# power.net
KiCad netlist of a schematic drawn in EAGLE
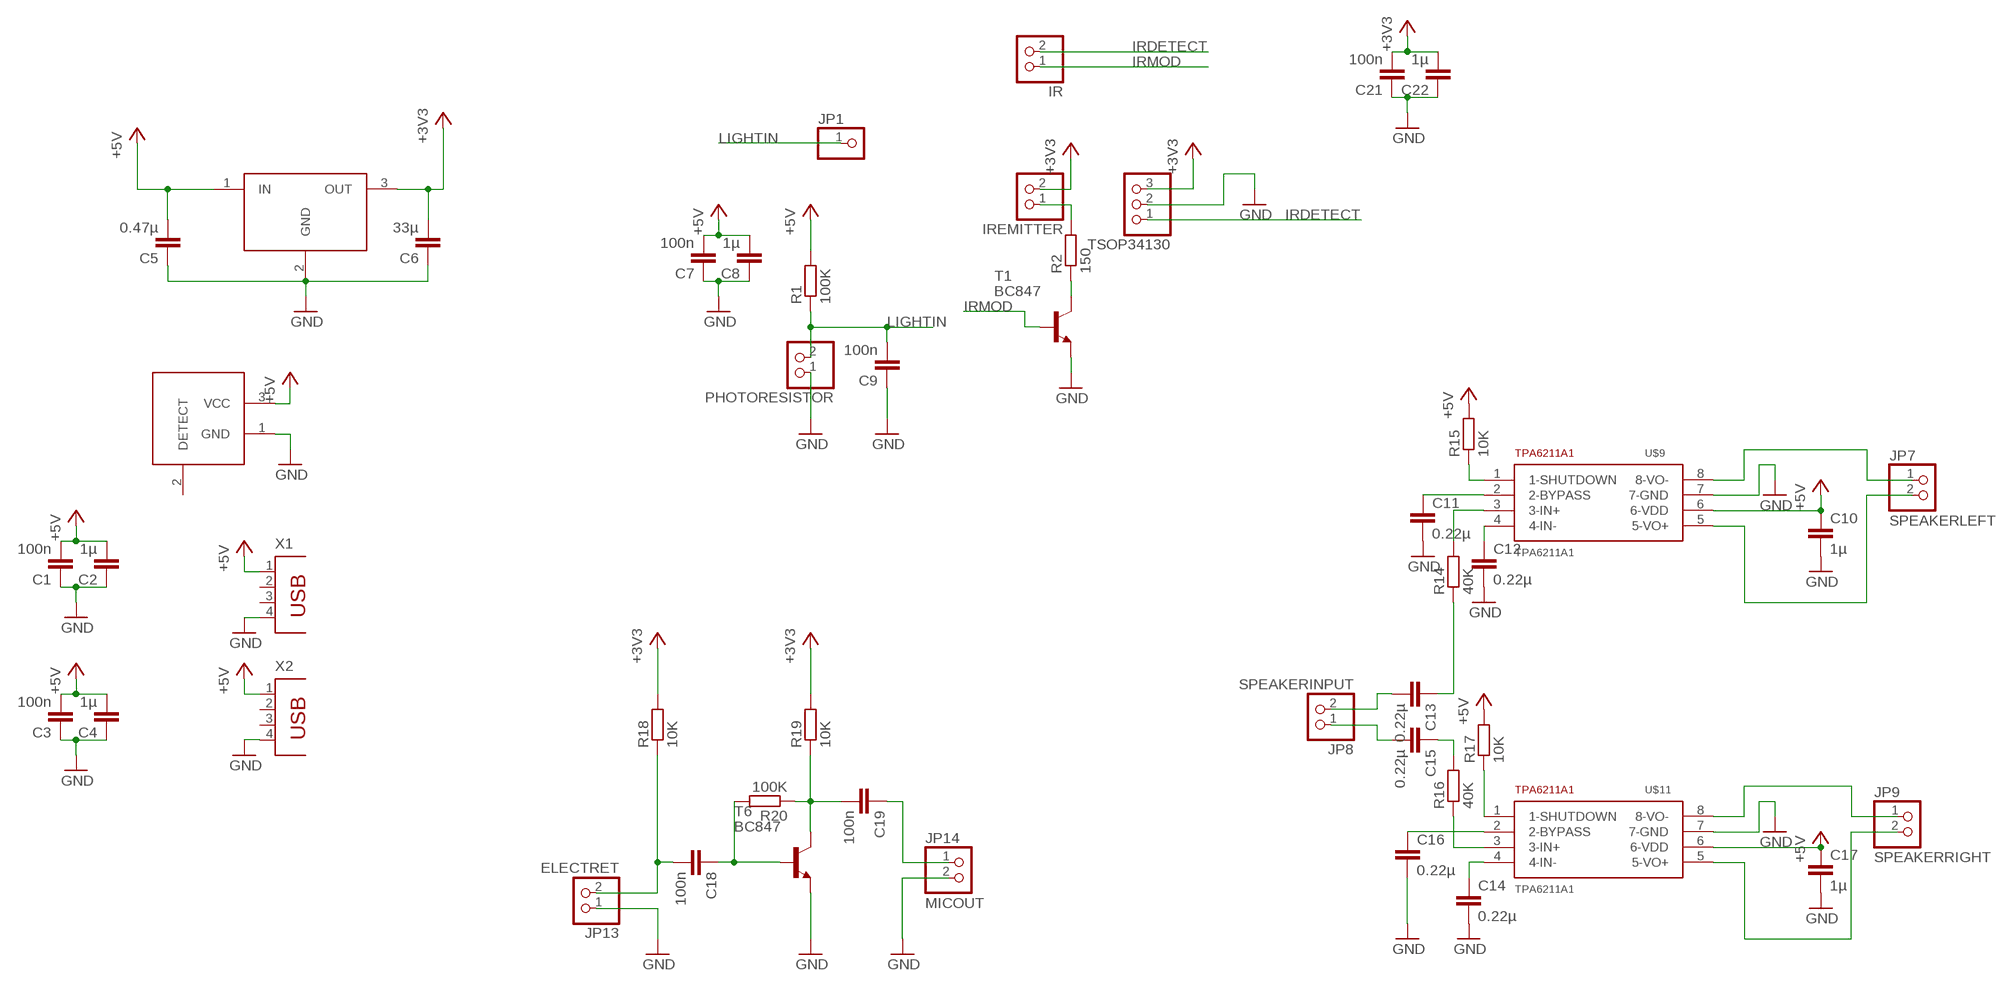
[diagram p0: schematic, sheet 1]

(export (version "E")
  (design (tool "Eeschema 10.0.6"))
  (components
    (comp (ref "C1")
      (value "100n")
      (footprint "eagle-import:C0805")
      (libsource (lib "eagle-import") (part "C-EUC0805"))
    )
    (comp (ref "C2")
      (value "1µ")
      (footprint "eagle-import:C0805")
      (libsource (lib "eagle-import") (part "C-EUC0805"))
    )
    (comp (ref "C3")
      (value "100n")
      (footprint "eagle-import:C0805")
      (libsource (lib "eagle-import") (part "C-EUC0805"))
    )
    (comp (ref "C4")
      (value "1µ")
      (footprint "eagle-import:C0805")
      (libsource (lib "eagle-import") (part "C-EUC0805"))
    )
    (comp (ref "C5")
      (value "0.47µ")
      (footprint "eagle-import:C0805")
      (libsource (lib "eagle-import") (part "C-EUC0805"))
    )
    (comp (ref "C6")
      (value "33µ")
      (footprint "eagle-import:C0805")
      (libsource (lib "eagle-import") (part "C-EUC0805"))
    )
    (comp (ref "C7")
      (value "100n")
      (footprint "eagle-import:C0805")
      (libsource (lib "eagle-import") (part "C-EUC0805"))
    )
    (comp (ref "C8")
      (value "1µ")
      (footprint "eagle-import:C0805")
      (libsource (lib "eagle-import") (part "C-EUC0805"))
    )
    (comp (ref "C9")
      (value "100n")
      (footprint "eagle-import:C0805")
      (libsource (lib "eagle-import") (part "C-EUC0805"))
    )
    (comp (ref "C10")
      (value "1µ")
      (footprint "eagle-import:C0805")
      (libsource (lib "eagle-import") (part "C-EUC0805"))
    )
    (comp (ref "C11")
      (value "0.22µ")
      (footprint "eagle-import:C0805")
      (libsource (lib "eagle-import") (part "C-EUC0805"))
    )
    (comp (ref "C12")
      (value "0.22µ")
      (footprint "eagle-import:C0805")
      (libsource (lib "eagle-import") (part "C-EUC0805"))
    )
    (comp (ref "C13")
      (value "0.22µ")
      (footprint "eagle-import:C0805")
      (libsource (lib "eagle-import") (part "C-EUC0805"))
    )
    (comp (ref "C14")
      (value "0.22µ")
      (footprint "eagle-import:C0805")
      (libsource (lib "eagle-import") (part "C-EUC0805"))
    )
    (comp (ref "C15")
      (value "0.22µ")
      (footprint "eagle-import:C0805")
      (libsource (lib "eagle-import") (part "C-EUC0805"))
    )
    (comp (ref "C16")
      (value "0.22µ")
      (footprint "eagle-import:C0805")
      (libsource (lib "eagle-import") (part "C-EUC0805"))
    )
    (comp (ref "C17")
      (value "1µ")
      (footprint "eagle-import:C0805")
      (libsource (lib "eagle-import") (part "C-EUC0805"))
    )
    (comp (ref "C18")
      (value "100n")
      (footprint "eagle-import:C0805")
      (libsource (lib "eagle-import") (part "C-EUC0805"))
    )
    (comp (ref "C19")
      (value "100n")
      (footprint "eagle-import:C0805")
      (libsource (lib "eagle-import") (part "C-EUC0805"))
    )
    (comp (ref "C21")
      (value "100n")
      (footprint "eagle-import:C0805")
      (libsource (lib "eagle-import") (part "C-EUC0805"))
    )
    (comp (ref "C22")
      (value "1µ")
      (footprint "eagle-import:C0805")
      (libsource (lib "eagle-import") (part "C-EUC0805"))
    )
    (comp (ref "IR")
      (value "PINHD-1X2")
      (footprint "eagle-import:1X02")
      (libsource (lib "eagle-import") (part "PINHD-1X2"))
    )
    (comp (ref "IREMITTER")
      (value "PINHD-1X2")
      (footprint "eagle-import:1X02")
      (libsource (lib "eagle-import") (part "PINHD-1X2"))
    )
    (comp (ref "JP1")
      (value "PINHD-1X1")
      (footprint "eagle-import:1X01")
      (libsource (lib "eagle-import") (part "PINHD-1X1"))
    )
    (comp (ref "JP7")
      (value "SPEAKERLEFT")
      (footprint "eagle-import:1X02")
      (libsource (lib "eagle-import") (part "PINHD-1X2"))
    )
    (comp (ref "JP8")
      (value "SPEAKERINPUT")
      (footprint "eagle-import:1X02")
      (libsource (lib "eagle-import") (part "PINHD-1X2"))
    )
    (comp (ref "JP9")
      (value "SPEAKERRIGHT")
      (footprint "eagle-import:1X02")
      (libsource (lib "eagle-import") (part "PINHD-1X2"))
    )
    (comp (ref "JP13")
      (value "ELECTRET")
      (footprint "eagle-import:1X02")
      (libsource (lib "eagle-import") (part "PINHD-1X2"))
    )
    (comp (ref "JP14")
      (value "MICOUT")
      (footprint "eagle-import:1X02")
      (libsource (lib "eagle-import") (part "PINHD-1X2"))
    )
    (comp (ref "PHOTORESISTOR")
      (value "PINHD-1X2")
      (footprint "eagle-import:1X02")
      (libsource (lib "eagle-import") (part "PINHD-1X2"))
    )
    (comp (ref "R1")
      (value "100K")
      (footprint "eagle-import:R0805")
      (libsource (lib "eagle-import") (part "R-EU_R0805"))
    )
    (comp (ref "R2")
      (value "150")
      (footprint "eagle-import:R0805")
      (libsource (lib "eagle-import") (part "R-EU_R0805"))
    )
    (comp (ref "R14")
      (value "40K")
      (footprint "eagle-import:R0805")
      (libsource (lib "eagle-import") (part "R-EU_R0805"))
    )
    (comp (ref "R15")
      (value "10K")
      (footprint "eagle-import:R0805")
      (libsource (lib "eagle-import") (part "R-EU_R0805"))
    )
    (comp (ref "R16")
      (value "40K")
      (footprint "eagle-import:R0805")
      (libsource (lib "eagle-import") (part "R-EU_R0805"))
    )
    (comp (ref "R17")
      (value "10K")
      (footprint "eagle-import:R0805")
      (libsource (lib "eagle-import") (part "R-EU_R0805"))
    )
    (comp (ref "R18")
      (value "10K")
      (footprint "eagle-import:R0805")
      (libsource (lib "eagle-import") (part "R-EU_R0805"))
    )
    (comp (ref "R19")
      (value "10K")
      (footprint "eagle-import:R0805")
      (libsource (lib "eagle-import") (part "R-EU_R0805"))
    )
    (comp (ref "R20")
      (value "100K")
      (footprint "eagle-import:R0805")
      (libsource (lib "eagle-import") (part "R-EU_R0805"))
    )
    (comp (ref "T1")
      (value "BC847")
      (footprint "eagle-import:SOT23")
      (libsource (lib "eagle-import") (part "BC847"))
    )
    (comp (ref "T6")
      (value "BC847")
      (footprint "eagle-import:SOT23")
      (libsource (lib "eagle-import") (part "BC847"))
    )
    (comp (ref "TSOP34130")
      (value "PINHD-1X3")
      (footprint "eagle-import:1X03")
      (libsource (lib "eagle-import") (part "PINHD-1X3"))
    )
    (comp (ref "U$1")
      (value "LM3940IMP-3.3")
      (footprint "eagle-import:SOT223")
      (libsource (lib "eagle-import") (part "LM3940IMP-3.3"))
    )
    (comp (ref "U$2")
      (value "POWERPLUG")
      (footprint "eagle-import:DC10LPSOCKET")
      (libsource (lib "eagle-import") (part "POWERPLUG"))
    )
    (comp (ref "U$9")
      (value "TPA6211A1")
      (footprint "eagle-import:MSOP8")
      (libsource (lib "eagle-import") (part "TPA6211A1"))
    )
    (comp (ref "U$11")
      (value "TPA6211A1")
      (footprint "eagle-import:MSOP8")
      (libsource (lib "eagle-import") (part "TPA6211A1"))
    )
    (comp (ref "X1")
      (value "PN87520")
      (footprint "eagle-import:PN87520")
      (libsource (lib "eagle-import") (part "PN87520"))
    )
    (comp (ref "X2")
      (value "PN87520")
      (footprint "eagle-import:PN87520")
      (libsource (lib "eagle-import") (part "PN87520"))
    )
  )
  (nets
    (net (code "1") (name "+3V3") (class "Default")
      (node (ref "C21") (pin "2") (pinfunction "2_2") (pintype "passive"))
      (node (ref "C22") (pin "2") (pinfunction "2_2") (pintype "passive"))
      (node (ref "C6") (pin "2") (pinfunction "2_2") (pintype "passive"))
      (node (ref "IREMITTER") (pin "2") (pinfunction "2_2") (pintype "passive"))
      (node (ref "R18") (pin "2") (pinfunction "2_2") (pintype "passive"))
      (node (ref "R19") (pin "2") (pinfunction "2_2") (pintype "passive"))
      (node (ref "TSOP34130") (pin "3") (pinfunction "3_3") (pintype "passive"))
      (node (ref "U$1") (pin "3") (pinfunction "OUT_3") (pintype "power_in"))
    )
    (net (code "2") (name "+5V") (class "Default")
      (node (ref "C1") (pin "2") (pinfunction "2_2") (pintype "passive"))
      (node (ref "C10") (pin "1") (pinfunction "1_1") (pintype "passive"))
      (node (ref "C17") (pin "1") (pinfunction "1_1") (pintype "passive"))
      (node (ref "C2") (pin "2") (pinfunction "2_2") (pintype "passive"))
      (node (ref "C3") (pin "2") (pinfunction "2_2") (pintype "passive"))
      (node (ref "C4") (pin "2") (pinfunction "2_2") (pintype "passive"))
      (node (ref "C5") (pin "2") (pinfunction "2_2") (pintype "passive"))
      (node (ref "C7") (pin "2") (pinfunction "2_2") (pintype "passive"))
      (node (ref "C8") (pin "2") (pinfunction "2_2") (pintype "passive"))
      (node (ref "R1") (pin "2") (pinfunction "2_2") (pintype "passive"))
      (node (ref "R15") (pin "2") (pinfunction "2_2") (pintype "passive"))
      (node (ref "R17") (pin "2") (pinfunction "2_2") (pintype "passive"))
      (node (ref "U$1") (pin "1") (pinfunction "IN_1") (pintype "power_in"))
      (node (ref "U$11") (pin "6") (pinfunction "6-VDD_6") (pintype "bidirectional"))
      (node (ref "U$2") (pin "3") (pinfunction "VCC_3") (pintype "bidirectional"))
      (node (ref "U$9") (pin "6") (pinfunction "6-VDD_6") (pintype "bidirectional"))
      (node (ref "X1") (pin "1") (pinfunction "1_1") (pintype "passive"))
      (node (ref "X2") (pin "1") (pinfunction "1_1") (pintype "passive"))
    )
    (net (code "3") (name "/IRDETECT") (class "Default")
      (node (ref "IR") (pin "2") (pinfunction "2_2") (pintype "passive"))
      (node (ref "TSOP34130") (pin "1") (pinfunction "1_1") (pintype "passive"))
    )
    (net (code "4") (name "/IRMOD") (class "Default")
      (node (ref "IR") (pin "1") (pinfunction "1_1") (pintype "passive"))
      (node (ref "T1") (pin "1") (pinfunction "B_1") (pintype "passive"))
    )
    (net (code "5") (name "/LIGHTIN") (class "Default")
      (node (ref "C9") (pin "2") (pinfunction "2_2") (pintype "passive"))
      (node (ref "JP1") (pin "1") (pinfunction "1_1") (pintype "passive"))
      (node (ref "PHOTORESISTOR") (pin "2") (pinfunction "2_2") (pintype "passive"))
      (node (ref "R1") (pin "1") (pinfunction "1_1") (pintype "passive"))
    )
    (net (code "6") (name "GND") (class "Default")
      (node (ref "C1") (pin "1") (pinfunction "1_1") (pintype "passive"))
      (node (ref "C10") (pin "2") (pinfunction "2_2") (pintype "passive"))
      (node (ref "C11") (pin "2") (pinfunction "2_2") (pintype "passive"))
      (node (ref "C12") (pin "2") (pinfunction "2_2") (pintype "passive"))
      (node (ref "C14") (pin "2") (pinfunction "2_2") (pintype "passive"))
      (node (ref "C16") (pin "2") (pinfunction "2_2") (pintype "passive"))
      (node (ref "C17") (pin "2") (pinfunction "2_2") (pintype "passive"))
      (node (ref "C2") (pin "1") (pinfunction "1_1") (pintype "passive"))
      (node (ref "C21") (pin "1") (pinfunction "1_1") (pintype "passive"))
      (node (ref "C22") (pin "1") (pinfunction "1_1") (pintype "passive"))
      (node (ref "C3") (pin "1") (pinfunction "1_1") (pintype "passive"))
      (node (ref "C4") (pin "1") (pinfunction "1_1") (pintype "passive"))
      (node (ref "C5") (pin "1") (pinfunction "1_1") (pintype "passive"))
      (node (ref "C6") (pin "1") (pinfunction "1_1") (pintype "passive"))
      (node (ref "C7") (pin "1") (pinfunction "1_1") (pintype "passive"))
      (node (ref "C8") (pin "1") (pinfunction "1_1") (pintype "passive"))
      (node (ref "C9") (pin "1") (pinfunction "1_1") (pintype "passive"))
      (node (ref "JP13") (pin "1") (pinfunction "1_1") (pintype "passive"))
      (node (ref "JP14") (pin "2") (pinfunction "2_2") (pintype "passive"))
      (node (ref "PHOTORESISTOR") (pin "1") (pinfunction "1_1") (pintype "passive"))
      (node (ref "T1") (pin "2") (pinfunction "E_2") (pintype "passive"))
      (node (ref "T6") (pin "2") (pinfunction "E_2") (pintype "passive"))
      (node (ref "TSOP34130") (pin "2") (pinfunction "2_2") (pintype "passive"))
      (node (ref "U$1") (pin "2") (pinfunction "GND_2") (pintype "power_in"))
      (node (ref "U$11") (pin "7") (pinfunction "7-GND_7") (pintype "bidirectional"))
      (node (ref "U$2") (pin "1") (pinfunction "GND_1") (pintype "bidirectional"))
      (node (ref "U$9") (pin "7") (pinfunction "7-GND_7") (pintype "bidirectional"))
      (node (ref "X1") (pin "4") (pinfunction "4_4") (pintype "passive"))
      (node (ref "X2") (pin "4") (pinfunction "4_4") (pintype "passive"))
    )
    (net (code "7") (name "Net-(C13-Pad1)") (class "Default")
      (node (ref "C13") (pin "1") (pinfunction "1_1") (pintype "passive"))
      (node (ref "R14") (pin "1") (pinfunction "1_1") (pintype "passive"))
    )
    (net (code "8") (name "Net-(C13-Pad2)") (class "Default")
      (node (ref "C13") (pin "2") (pinfunction "2_2") (pintype "passive"))
      (node (ref "JP8") (pin "2") (pinfunction "2_2") (pintype "passive"))
    )
    (net (code "9") (name "Net-(C15-Pad1)") (class "Default")
      (node (ref "C15") (pin "1") (pinfunction "1_1") (pintype "passive"))
      (node (ref "R16") (pin "2") (pinfunction "2_2") (pintype "passive"))
    )
    (net (code "10") (name "Net-(C15-Pad2)") (class "Default")
      (node (ref "C15") (pin "2") (pinfunction "2_2") (pintype "passive"))
      (node (ref "JP8") (pin "1") (pinfunction "1_1") (pintype "passive"))
    )
    (net (code "11") (name "Net-(C18-Pad2)") (class "Default")
      (node (ref "C18") (pin "2") (pinfunction "2_2") (pintype "passive"))
      (node (ref "JP13") (pin "2") (pinfunction "2_2") (pintype "passive"))
      (node (ref "R18") (pin "1") (pinfunction "1_1") (pintype "passive"))
    )
    (net (code "12") (name "Net-(C19-Pad1)") (class "Default")
      (node (ref "C19") (pin "1") (pinfunction "1_1") (pintype "passive"))
      (node (ref "JP14") (pin "1") (pinfunction "1_1") (pintype "passive"))
    )
    (net (code "13") (name "Net-(IREMITTER-Pad1)") (class "Default")
      (node (ref "IREMITTER") (pin "1") (pinfunction "1_1") (pintype "passive"))
      (node (ref "R2") (pin "2") (pinfunction "2_2") (pintype "passive"))
    )
    (net (code "14") (name "Net-(T1-C)") (class "Default")
      (node (ref "R2") (pin "1") (pinfunction "1_1") (pintype "passive"))
      (node (ref "T1") (pin "3") (pinfunction "C_3") (pintype "passive"))
    )
    (net (code "15") (name "Net-(T6-B)") (class "Default")
      (node (ref "C18") (pin "1") (pinfunction "1_1") (pintype "passive"))
      (node (ref "R20") (pin "2") (pinfunction "2_2") (pintype "passive"))
      (node (ref "T6") (pin "1") (pinfunction "B_1") (pintype "passive"))
    )
    (net (code "16") (name "Net-(T6-C)") (class "Default")
      (node (ref "C19") (pin "2") (pinfunction "2_2") (pintype "passive"))
      (node (ref "R19") (pin "1") (pinfunction "1_1") (pintype "passive"))
      (node (ref "R20") (pin "1") (pinfunction "1_1") (pintype "passive"))
      (node (ref "T6") (pin "3") (pinfunction "C_3") (pintype "passive"))
    )
    (net (code "17") (name "Net-(U$9-1-SHUTDOWN)") (class "Default")
      (node (ref "R15") (pin "1") (pinfunction "1_1") (pintype "passive"))
      (node (ref "U$9") (pin "1") (pinfunction "1-SHUTDOWN_1") (pintype "bidirectional"))
    )
    (net (code "18") (name "Net-(U$9-2-BYPASS)") (class "Default")
      (node (ref "C11") (pin "1") (pinfunction "1_1") (pintype "passive"))
      (node (ref "U$9") (pin "2") (pinfunction "2-BYPASS_2") (pintype "bidirectional"))
    )
    (net (code "19") (name "Net-(U$9-3-IN+)") (class "Default")
      (node (ref "R14") (pin "2") (pinfunction "2_2") (pintype "passive"))
      (node (ref "U$9") (pin "3") (pinfunction "3-IN+_3") (pintype "bidirectional"))
    )
    (net (code "20") (name "Net-(U$9-4-IN-)") (class "Default")
      (node (ref "C12") (pin "1") (pinfunction "1_1") (pintype "passive"))
      (node (ref "U$9") (pin "4") (pinfunction "4-IN-_4") (pintype "bidirectional"))
    )
    (net (code "21") (name "Net-(U$9-5-VO+)") (class "Default")
      (node (ref "JP7") (pin "2") (pinfunction "2_2") (pintype "passive"))
      (node (ref "U$9") (pin "5") (pinfunction "5-VO+_5") (pintype "bidirectional"))
    )
    (net (code "22") (name "Net-(U$9-8-VO-)") (class "Default")
      (node (ref "JP7") (pin "1") (pinfunction "1_1") (pintype "passive"))
      (node (ref "U$9") (pin "8") (pinfunction "8-VO-_8") (pintype "bidirectional"))
    )
    (net (code "23") (name "Net-(U$11-1-SHUTDOWN)") (class "Default")
      (node (ref "R17") (pin "1") (pinfunction "1_1") (pintype "passive"))
      (node (ref "U$11") (pin "1") (pinfunction "1-SHUTDOWN_1") (pintype "bidirectional"))
    )
    (net (code "24") (name "Net-(U$11-2-BYPASS)") (class "Default")
      (node (ref "C16") (pin "1") (pinfunction "1_1") (pintype "passive"))
      (node (ref "U$11") (pin "2") (pinfunction "2-BYPASS_2") (pintype "bidirectional"))
    )
    (net (code "25") (name "Net-(U$11-3-IN+)") (class "Default")
      (node (ref "R16") (pin "1") (pinfunction "1_1") (pintype "passive"))
      (node (ref "U$11") (pin "3") (pinfunction "3-IN+_3") (pintype "bidirectional"))
    )
    (net (code "26") (name "Net-(U$11-4-IN-)") (class "Default")
      (node (ref "C14") (pin "1") (pinfunction "1_1") (pintype "passive"))
      (node (ref "U$11") (pin "4") (pinfunction "4-IN-_4") (pintype "bidirectional"))
    )
    (net (code "27") (name "Net-(U$11-5-VO+)") (class "Default")
      (node (ref "JP9") (pin "2") (pinfunction "2_2") (pintype "passive"))
      (node (ref "U$11") (pin "5") (pinfunction "5-VO+_5") (pintype "bidirectional"))
    )
    (net (code "28") (name "Net-(U$11-8-VO-)") (class "Default")
      (node (ref "JP9") (pin "1") (pinfunction "1_1") (pintype "passive"))
      (node (ref "U$11") (pin "8") (pinfunction "8-VO-_8") (pintype "bidirectional"))
    )
    (net (code "29") (name "unconnected-(U$2-DETECT-Pad2)") (class "Default")
      (node (ref "U$2") (pin "2") (pinfunction "DETECT_2") (pintype "bidirectional"))
    )
    (net (code "30") (name "unconnected-(X1-Pad2)") (class "Default")
      (node (ref "X1") (pin "2") (pinfunction "2_2") (pintype "passive"))
    )
    (net (code "31") (name "unconnected-(X1-Pad3)") (class "Default")
      (node (ref "X1") (pin "3") (pinfunction "3_3") (pintype "passive"))
    )
    (net (code "32") (name "unconnected-(X2-Pad2)") (class "Default")
      (node (ref "X2") (pin "2") (pinfunction "2_2") (pintype "passive"))
    )
    (net (code "33") (name "unconnected-(X2-Pad3)") (class "Default")
      (node (ref "X2") (pin "3") (pinfunction "3_3") (pintype "passive"))
    )
  )
)
